# Laser_driver_adj_3A_TTL.net
KiCad netlist of a schematic drawn in Altium Designer
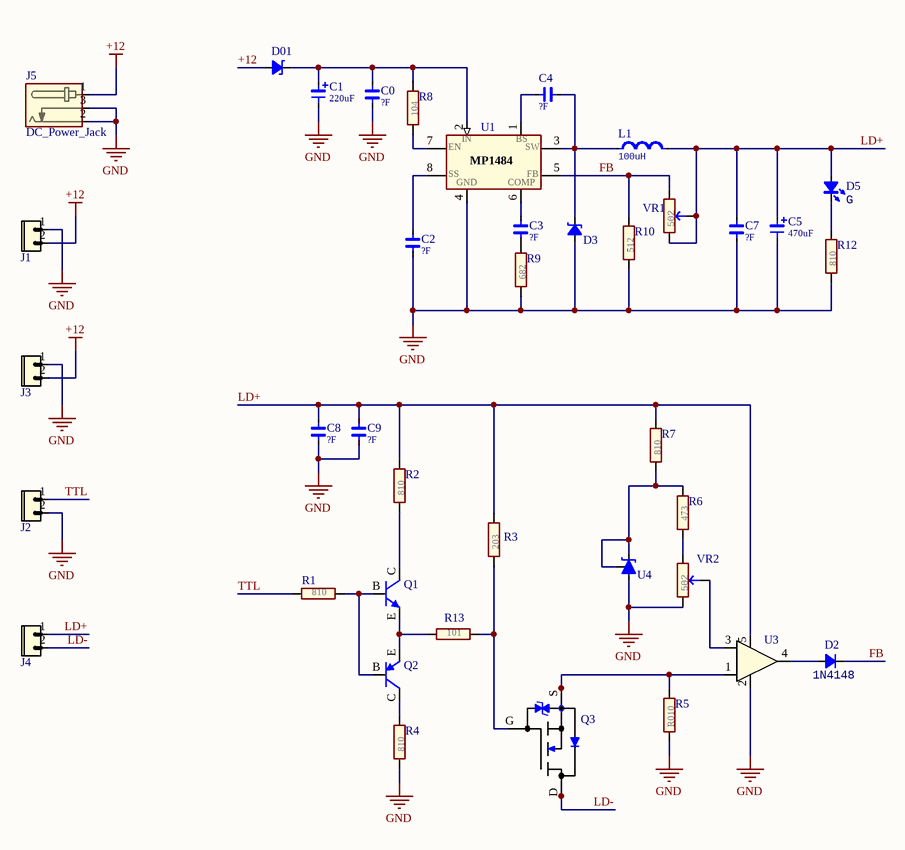
[diagram p0: Laser_driver_adj_3A_TTL.SchDoc]

(export (version "E")
  (design (tool "Eeschema 10.0.6"))
  (components
    (comp (ref "C0")
      (value "?F")
      (footprint "CAP_0603")
      (fields (field (name "Comment") "Cap"))
      (libsource (lib "Passive") (part "Cap"))
    )
    (comp (ref "C1")
      (value "220uF")
      (footprint "CAP_PR_SMD_6.3")
      (fields (field (name "Comment") "Cap_P"))
      (libsource (lib "Passive") (part "Cap_P"))
    )
    (comp (ref "C2")
      (value "?F")
      (footprint "CAP_0603")
      (fields (field (name "Comment") "Cap"))
      (libsource (lib "Passive") (part "Cap"))
    )
    (comp (ref "C3")
      (value "?F")
      (footprint "CAP_0603")
      (fields (field (name "Comment") "Cap"))
      (libsource (lib "Passive") (part "Cap"))
    )
    (comp (ref "C4")
      (value "?F")
      (footprint "CAP_0603")
      (fields (field (name "Comment") "Cap"))
      (libsource (lib "") (part "Cap_2"))
    )
    (comp (ref "C5")
      (value "470uF")
      (footprint "CAP_PR_SMD_8.3")
      (fields (field (name "Comment") "Cap_P"))
      (libsource (lib "Passive") (part "Cap_P"))
    )
    (comp (ref "C7")
      (value "?F")
      (footprint "CAP_0603")
      (fields (field (name "Comment") "Cap"))
      (libsource (lib "") (part "Cap_1"))
    )
    (comp (ref "C8")
      (value "?F")
      (footprint "CAP_0603")
      (fields (field (name "Comment") "Cap"))
      (libsource (lib "") (part "Cap_1"))
    )
    (comp (ref "C9")
      (value "?F")
      (footprint "CAP_0603")
      (fields (field (name "Comment") "Cap"))
      (libsource (lib "") (part "Cap_1"))
    )
    (comp (ref "D01")
      (value "~")
      (footprint "DO-214AC")
      (description "Schottky Diode")
      (libsource (lib "Active") (part "SchottkyDiode"))
    )
    (comp (ref "D2")
      (value "1N4148")
      (footprint "SOD-80/MLL34")
      (description "Diode")
      (libsource (lib "Active") (part "Diode"))
    )
    (comp (ref "D3")
      (value "~")
      (footprint "DO-214AC")
      (description "Schottky Diode")
      (libsource (lib "Active") (part "SchottkyDiode"))
    )
    (comp (ref "D5")
      (value "G")
      (footprint "LED_0603")
      (description "LED")
      (libsource (lib "Active") (part "LED"))
    )
    (comp (ref "J1")
      (value "CON_XH2.54_2")
      (footprint "XH2.54_2")
      (libsource (lib "Connector") (part "CON_XH2.54_2"))
    )
    (comp (ref "J2")
      (value "CON_XH2.54_2")
      (footprint "XH2.54_2")
      (libsource (lib "Connector") (part "CON_XH2.54_2"))
    )
    (comp (ref "J3")
      (value "CON_XH2.54_2")
      (footprint "XH2.54_2")
      (libsource (lib "Connector") (part "CON_XH2.54_2"))
    )
    (comp (ref "J4")
      (value "CON_XH2.54_2")
      (footprint "XH2.54_2")
      (libsource (lib "Connector") (part "CON_XH2.54_2"))
    )
    (comp (ref "J5")
      (value "DC_Power_Jack")
      (footprint "DC005")
      (libsource (lib "Connector") (part "DC_Power_Jack"))
    )
    (comp (ref "L1")
      (value "100uH")
      (footprint "IND_SLF10145")
      (description "Inductor")
      (fields (field (name "Comment") "Ind"))
      (libsource (lib "Passive") (part "Ind"))
    )
    (comp (ref "Q1")
      (value "NPN")
      (footprint "SOT23-3M")
      (description "NPN General Purpose Amplifier")
      (fields (field (name "PUBLISHER") "Altium Limited"))
      (libsource (lib "Tri") (part "NPN"))
    )
    (comp (ref "Q2")
      (value "PNP")
      (footprint "SOT23-3M")
      (description "PNP General Purpose Amplifier")
      (fields (field (name "PUBLISHER") "Altium Limited"))
      (libsource (lib "Tri") (part "PNP"))
    )
    (comp (ref "Q3") (value "RSS100N003") (footprint "SOP8_M") (libsource (lib "MOSFET") (part "RSS100N003")))
    (comp (ref "R1")
      (value "810")
      (footprint "RES_0603")
      (fields (field (name "Comment") "Res"))
      (libsource (lib "") (part "Res_2"))
    )
    (comp (ref "R2")
      (value "810")
      (footprint "RES_0603")
      (fields (field (name "Comment") "Res"))
      (libsource (lib "Passive") (part "Res"))
    )
    (comp (ref "R3")
      (value "203")
      (footprint "RES_0603")
      (fields (field (name "Comment") "Res"))
      (libsource (lib "Passive") (part "Res"))
    )
    (comp (ref "R4")
      (value "810")
      (footprint "RES_0603")
      (fields (field (name "Comment") "Res"))
      (libsource (lib "Passive") (part "Res"))
    )
    (comp (ref "R5")
      (value "R010")
      (footprint "RES_2512M")
      (fields (field (name "Comment") "Res"))
      (libsource (lib "Passive") (part "Res"))
    )
    (comp (ref "R6")
      (value "473")
      (footprint "RES_0603")
      (fields (field (name "Comment") "Res"))
      (libsource (lib "Passive") (part "Res"))
    )
    (comp (ref "R7")
      (value "810")
      (footprint "RES_0603")
      (fields (field (name "Comment") "Res"))
      (libsource (lib "") (part "Res_1"))
    )
    (comp (ref "R8")
      (value "104")
      (footprint "RES_0603")
      (fields (field (name "Comment") "Res"))
      (libsource (lib "Passive") (part "Res"))
    )
    (comp (ref "R9")
      (value "682")
      (footprint "RES_0603")
      (fields (field (name "Comment") "Res"))
      (libsource (lib "Passive") (part "Res"))
    )
    (comp (ref "R10")
      (value "512")
      (footprint "RES_0603")
      (fields (field (name "Comment") "Res"))
      (libsource (lib "Passive") (part "Res"))
    )
    (comp (ref "R12")
      (value "810")
      (footprint "RES_0603")
      (fields (field (name "Comment") "Res"))
      (libsource (lib "") (part "Res_1"))
    )
    (comp (ref "R13")
      (value "101")
      (footprint "RES_0603")
      (fields (field (name "Comment") "Res"))
      (libsource (lib "") (part "Res_2"))
    )
    (comp (ref "U1") (value "MP1484") (footprint "SOIC8N") (libsource (lib "Regulator") (part "MP1484")))
    (comp (ref "U3") (value "LMV321") (footprint "SOT23-5AM") (libsource (lib "OPA") (part "LMV321")))
    (comp (ref "U4") (value "TL432") (footprint "SOT23-3M") (libsource (lib "Regulator") (part "TL432")))
    (comp (ref "VR1")
      (value "502")
      (footprint "RES_VR_EVM3G/E")
      (description "Resistor Variable")
      (fields (field (name "Comment") "VR"))
      (libsource (lib "Passive") (part "Res_VR"))
    )
    (comp (ref "VR2")
      (value "502")
      (footprint "RES_VR_3296W")
      (description "Resistor Variable")
      (fields (field (name "Comment") "VR"))
      (libsource (lib "Passive") (part "Res_VR"))
    )
  )
  (nets
    (net (code "1") (name "+12") (class "Default")
      (node (ref "D01") (pin "1") (pinfunction "A_1") (pintype "passive"))
      (node (ref "J1") (pin "2") (pinfunction "2_2") (pintype "passive"))
      (node (ref "J3") (pin "2") (pinfunction "2_2") (pintype "passive"))
      (node (ref "J5") (pin "1") (pinfunction "1_1") (pintype "passive"))
    )
    (net (code "2") (name "/FB") (class "Default")
      (node (ref "D2") (pin "2") (pinfunction "K_2") (pintype "passive"))
      (node (ref "R10") (pin "2") (pinfunction "2_2") (pintype "passive"))
      (node (ref "U1") (pin "5") (pinfunction "FB_5") (pintype "passive"))
      (node (ref "VR1") (pin "1") (pinfunction "1_1") (pintype "passive"))
    )
    (net (code "3") (name "/LD+") (class "Default")
      (node (ref "C5") (pin "1") (pinfunction "1_1") (pintype "passive"))
      (node (ref "C7") (pin "2") (pinfunction "2_2") (pintype "passive"))
      (node (ref "C8") (pin "2") (pinfunction "2_2") (pintype "passive"))
      (node (ref "C9") (pin "2") (pinfunction "2_2") (pintype "passive"))
      (node (ref "D5") (pin "1") (pinfunction "A_1") (pintype "passive"))
      (node (ref "J4") (pin "1") (pinfunction "1_1") (pintype "passive"))
      (node (ref "L1") (pin "2") (pinfunction "2_2") (pintype "passive"))
      (node (ref "R2") (pin "2") (pinfunction "2_2") (pintype "passive"))
      (node (ref "R3") (pin "2") (pinfunction "2_2") (pintype "passive"))
      (node (ref "R7") (pin "1") (pinfunction "1_1") (pintype "passive"))
      (node (ref "U3") (pin "5") (pinfunction "V+_5") (pintype "passive"))
      (node (ref "VR1") (pin "2") (pinfunction "2_2") (pintype "passive"))
      (node (ref "VR1") (pin "3") (pinfunction "3_3") (pintype "passive"))
    )
    (net (code "4") (name "/LD-") (class "Default")
      (node (ref "J4") (pin "2") (pinfunction "2_2") (pintype "passive"))
      (node (ref "Q3") (pin "D") (pinfunction "D_D") (pintype "passive"))
      (node (ref "Q3") (pin "DD") (pinfunction "DD_DD") (pintype "passive"))
      (node (ref "Q3") (pin "DDD") (pinfunction "DDD_DDD") (pintype "passive"))
      (node (ref "Q3") (pin "DDDD") (pinfunction "DDDD_DDDD") (pintype "passive"))
    )
    (net (code "5") (name "/TTL") (class "Default")
      (node (ref "J2") (pin "1") (pinfunction "1_1") (pintype "passive"))
      (node (ref "R1") (pin "2") (pinfunction "2_2") (pintype "passive"))
    )
    (net (code "6") (name "GND") (class "Default")
      (node (ref "C0") (pin "2") (pinfunction "2_2") (pintype "passive"))
      (node (ref "C1") (pin "2") (pinfunction "2_2") (pintype "passive"))
      (node (ref "C2") (pin "2") (pinfunction "2_2") (pintype "passive"))
      (node (ref "C5") (pin "2") (pinfunction "2_2") (pintype "passive"))
      (node (ref "C7") (pin "1") (pinfunction "1_1") (pintype "passive"))
      (node (ref "C8") (pin "1") (pinfunction "1_1") (pintype "passive"))
      (node (ref "C9") (pin "1") (pinfunction "1_1") (pintype "passive"))
      (node (ref "D3") (pin "1") (pinfunction "A_1") (pintype "passive"))
      (node (ref "J1") (pin "1") (pinfunction "1_1") (pintype "passive"))
      (node (ref "J2") (pin "2") (pinfunction "2_2") (pintype "passive"))
      (node (ref "J3") (pin "1") (pinfunction "1_1") (pintype "passive"))
      (node (ref "J5") (pin "2") (pinfunction "2_2") (pintype "passive"))
      (node (ref "J5") (pin "3") (pinfunction "3_3") (pintype "passive"))
      (node (ref "R10") (pin "1") (pinfunction "1_1") (pintype "passive"))
      (node (ref "R12") (pin "2") (pinfunction "2_2") (pintype "passive"))
      (node (ref "R4") (pin "1") (pinfunction "1_1") (pintype "passive"))
      (node (ref "R5") (pin "1") (pinfunction "1_1") (pintype "passive"))
      (node (ref "R9") (pin "1") (pinfunction "1_1") (pintype "passive"))
      (node (ref "U1") (pin "4") (pinfunction "GND_4") (pintype "power_in"))
      (node (ref "U3") (pin "2") (pinfunction "V-_2") (pintype "passive"))
      (node (ref "U4") (pin "A") (pinfunction "ANODE_A") (pintype "passive"))
      (node (ref "VR2") (pin "3") (pinfunction "3_3") (pintype "passive"))
    )
    (net (code "7") (name "Net-(C3-Pad1)") (class "Default")
      (node (ref "C3") (pin "1") (pinfunction "1_1") (pintype "passive"))
      (node (ref "U1") (pin "6") (pinfunction "IN_6") (pintype "passive"))
    )
    (net (code "8") (name "Net-(C3-Pad2)") (class "Default")
      (node (ref "C3") (pin "2") (pinfunction "2_2") (pintype "passive"))
      (node (ref "R9") (pin "2") (pinfunction "2_2") (pintype "passive"))
    )
    (net (code "9") (name "Net-(D01-K)") (class "Default")
      (node (ref "C0") (pin "1") (pinfunction "1_1") (pintype "passive"))
      (node (ref "C1") (pin "1") (pinfunction "1_1") (pintype "passive"))
      (node (ref "D01") (pin "2") (pinfunction "K_2") (pintype "passive"))
      (node (ref "R8") (pin "2") (pinfunction "2_2") (pintype "passive"))
      (node (ref "U1") (pin "2") (pinfunction "IN_2") (pintype "input"))
    )
    (net (code "10") (name "Net-(D2-A)") (class "Default")
      (node (ref "D2") (pin "1") (pinfunction "A_1") (pintype "passive"))
      (node (ref "U3") (pin "4") (pinfunction "OUTPUT_4") (pintype "passive"))
    )
    (net (code "11") (name "Net-(D3-K)") (class "Default")
      (node (ref "C4") (pin "2") (pinfunction "2_2") (pintype "passive"))
      (node (ref "D3") (pin "2") (pinfunction "K_2") (pintype "passive"))
      (node (ref "L1") (pin "1") (pinfunction "1_1") (pintype "passive"))
      (node (ref "U1") (pin "3") (pinfunction "SW_3") (pintype "passive"))
    )
    (net (code "12") (name "Net-(D5-K)") (class "Default")
      (node (ref "D5") (pin "2") (pinfunction "K_2") (pintype "passive"))
      (node (ref "R12") (pin "1") (pinfunction "1_1") (pintype "passive"))
    )
    (net (code "13") (name "Net-(Q1-PadB)") (class "Default")
      (node (ref "Q1") (pin "B") (pinfunction "B_B") (pintype "passive"))
      (node (ref "Q2") (pin "B") (pinfunction "B_B") (pintype "passive"))
      (node (ref "R1") (pin "1") (pinfunction "1_1") (pintype "passive"))
    )
    (net (code "14") (name "Net-(Q1-PadC)") (class "Default")
      (node (ref "Q1") (pin "C") (pinfunction "C_C") (pintype "passive"))
      (node (ref "R2") (pin "1") (pinfunction "1_1") (pintype "passive"))
    )
    (net (code "15") (name "Net-(Q1-PadE)") (class "Default")
      (node (ref "Q1") (pin "E") (pinfunction "E_E") (pintype "passive"))
      (node (ref "Q2") (pin "E") (pinfunction "E_E") (pintype "passive"))
      (node (ref "R13") (pin "2") (pinfunction "2_2") (pintype "passive"))
    )
    (net (code "16") (name "Net-(Q2-PadC)") (class "Default")
      (node (ref "Q2") (pin "C") (pinfunction "C_C") (pintype "passive"))
      (node (ref "R4") (pin "2") (pinfunction "2_2") (pintype "passive"))
    )
    (net (code "17") (name "Net-(Q3-PadG)") (class "Default")
      (node (ref "Q3") (pin "G") (pinfunction "G_G") (pintype "passive"))
      (node (ref "R13") (pin "1") (pinfunction "1_1") (pintype "passive"))
      (node (ref "R3") (pin "1") (pinfunction "1_1") (pintype "passive"))
    )
    (net (code "18") (name "Net-(R6-Pad1)") (class "Default")
      (node (ref "R6") (pin "1") (pinfunction "1_1") (pintype "passive"))
      (node (ref "VR2") (pin "1") (pinfunction "1_1") (pintype "passive"))
    )
    (net (code "19") (name "Net-(U1-BS)") (class "Default")
      (node (ref "C4") (pin "1") (pinfunction "1_1") (pintype "passive"))
      (node (ref "U1") (pin "1") (pinfunction "BS_1") (pintype "passive"))
    )
    (net (code "20") (name "Net-(U1-EN)") (class "Default")
      (node (ref "R8") (pin "1") (pinfunction "1_1") (pintype "passive"))
      (node (ref "U1") (pin "7") (pinfunction "EN_7") (pintype "passive"))
    )
    (net (code "21") (name "Net-(U1-SS)") (class "Default")
      (node (ref "C2") (pin "1") (pinfunction "1_1") (pintype "passive"))
      (node (ref "U1") (pin "8") (pinfunction "SS_8") (pintype "passive"))
    )
    (net (code "22") (name "Net-(U3-+IN)") (class "Default")
      (node (ref "Q3") (pin "S") (pinfunction "S_S") (pintype "passive"))
      (node (ref "Q3") (pin "SS") (pinfunction "SS_SS") (pintype "passive"))
      (node (ref "Q3") (pin "SSS") (pinfunction "SSS_SSS") (pintype "passive"))
      (node (ref "R5") (pin "2") (pinfunction "2_2") (pintype "passive"))
      (node (ref "U3") (pin "1") (pinfunction "+IN_1") (pintype "passive"))
    )
    (net (code "23") (name "Net-(U3--IN)") (class "Default")
      (node (ref "U3") (pin "3") (pinfunction "-IN_3") (pintype "passive"))
      (node (ref "VR2") (pin "2") (pinfunction "2_2") (pintype "passive"))
    )
    (net (code "24") (name "Net-(U4-CATHODE)") (class "Default")
      (node (ref "R6") (pin "2") (pinfunction "2_2") (pintype "passive"))
      (node (ref "R7") (pin "2") (pinfunction "2_2") (pintype "passive"))
      (node (ref "U4") (pin "C") (pinfunction "CATHODE_C") (pintype "passive"))
      (node (ref "U4") (pin "R") (pinfunction "REF_R") (pintype "passive"))
    )
  )
)
